# SCH_Base-robot_2026-06-25.net
KiCad netlist of a schematic drawn in EasyEDA
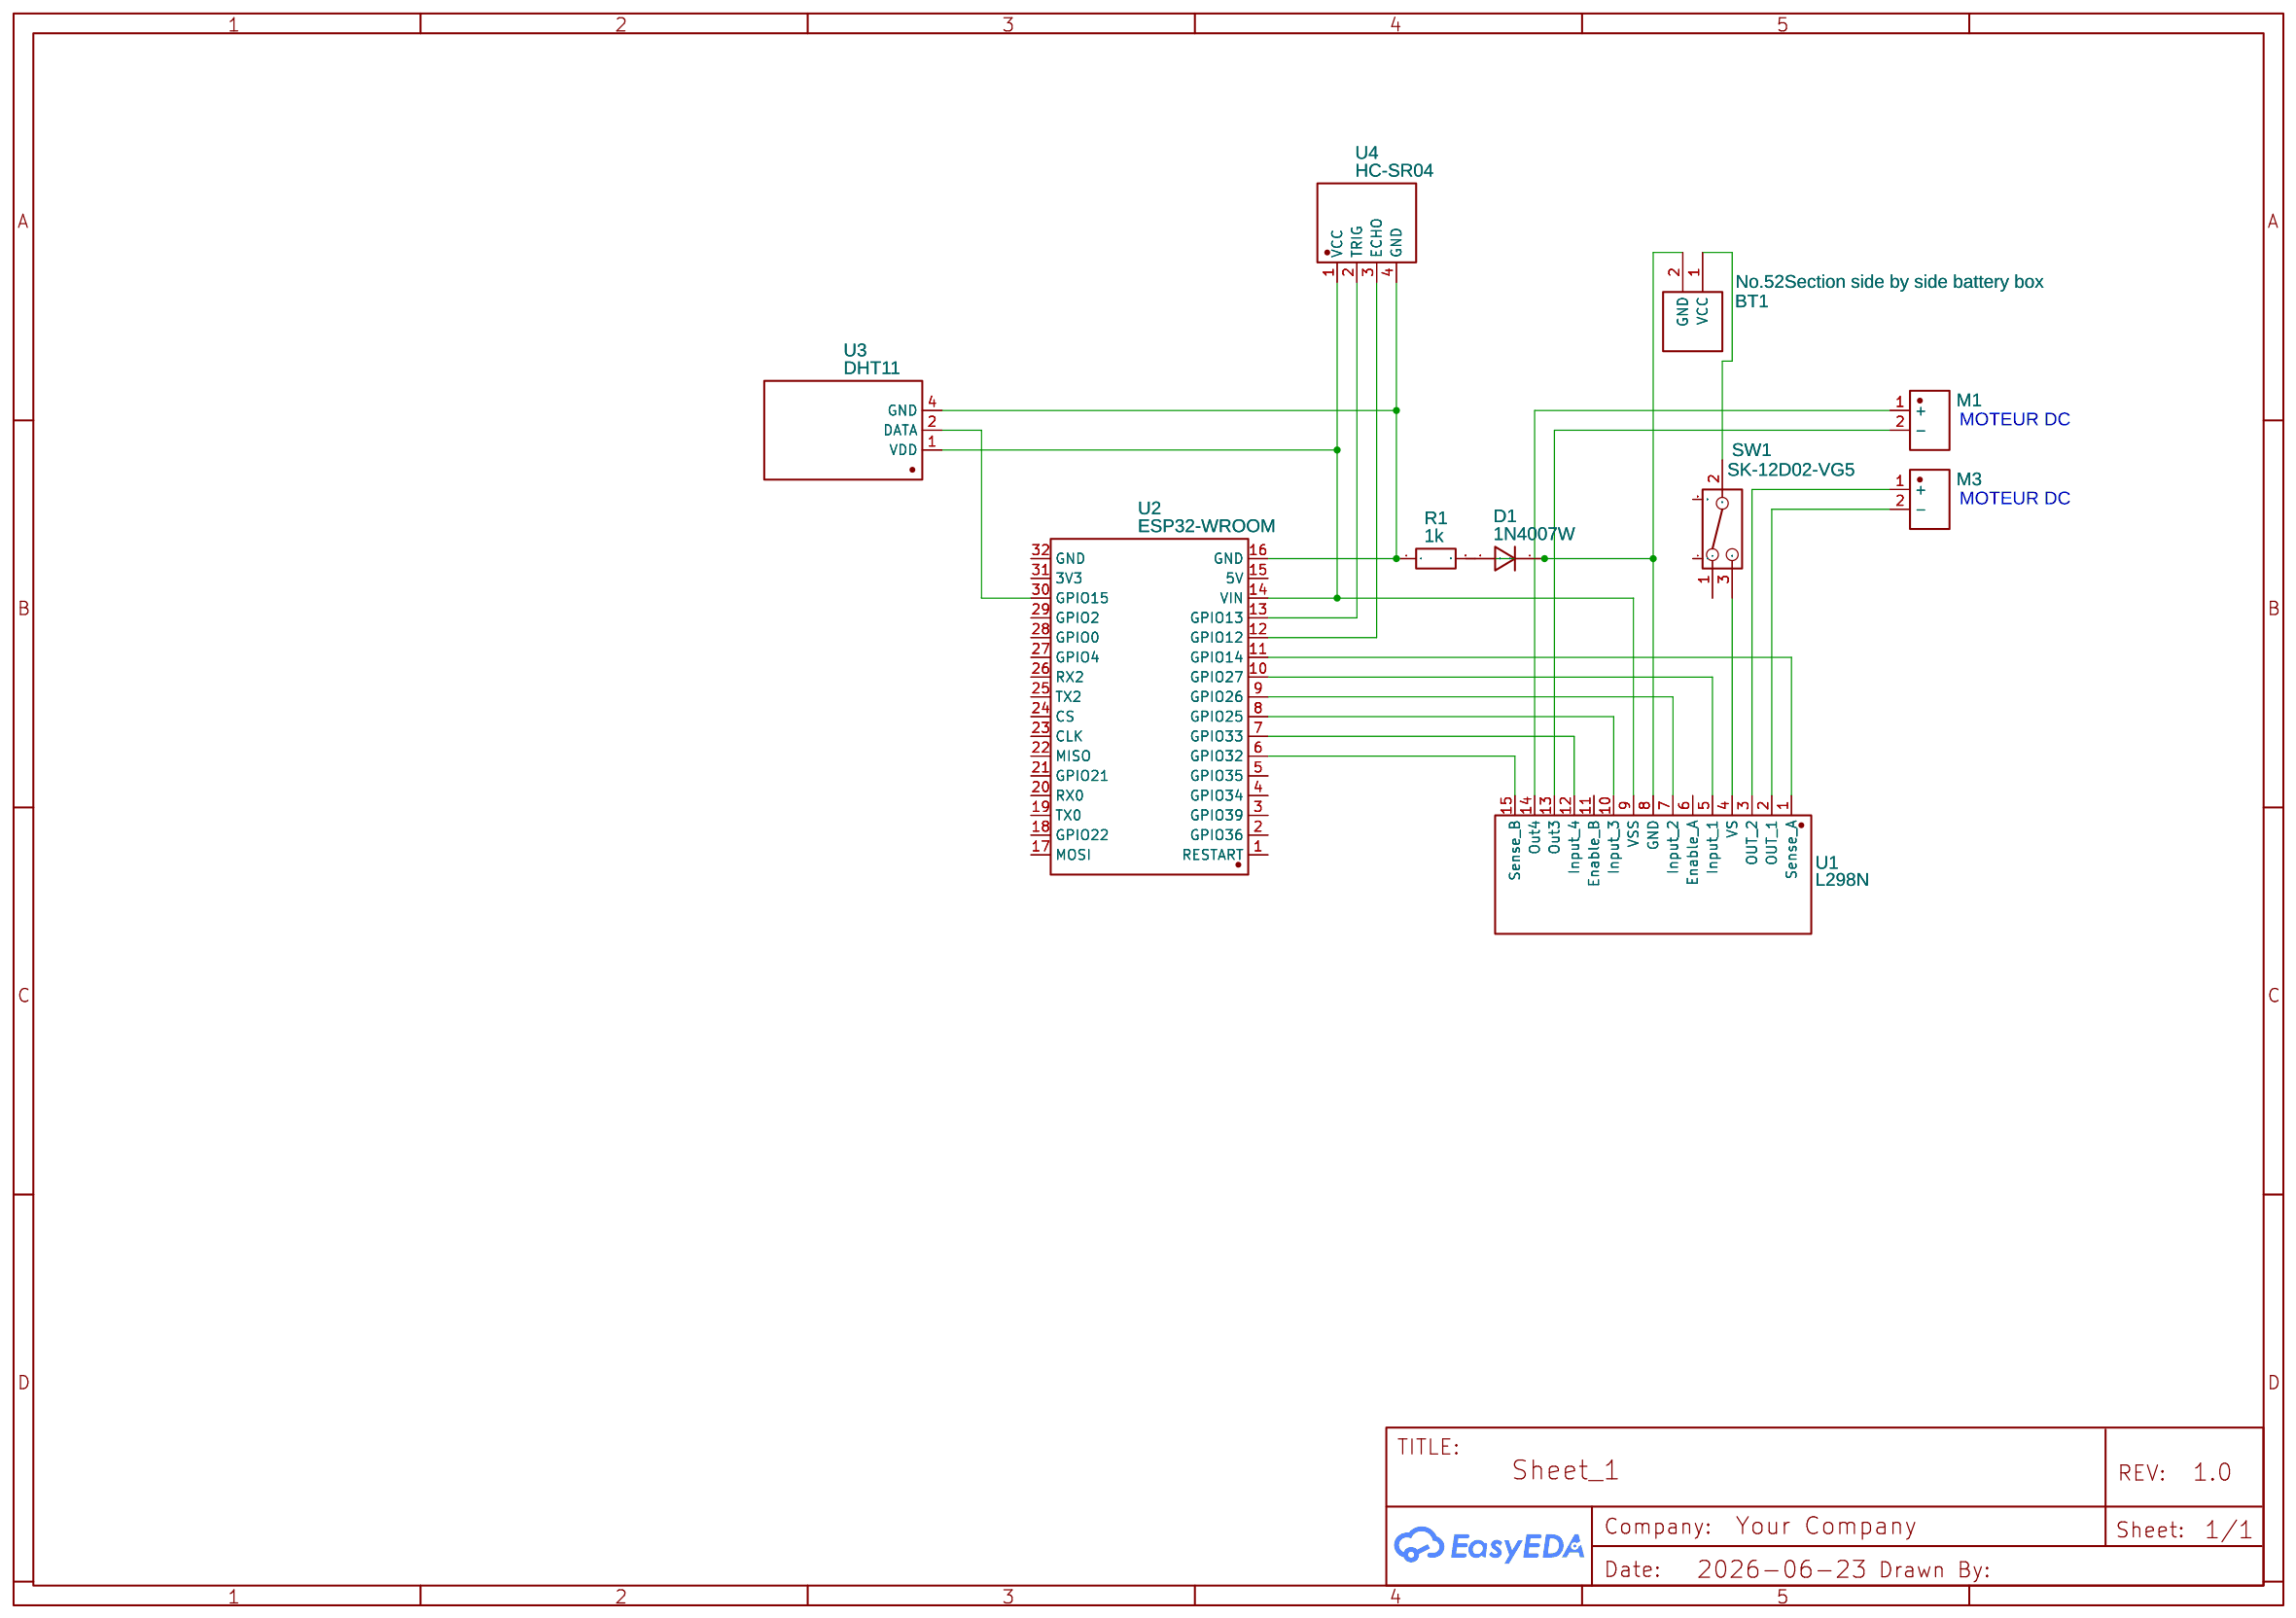
[diagram p0: Base Roulante]
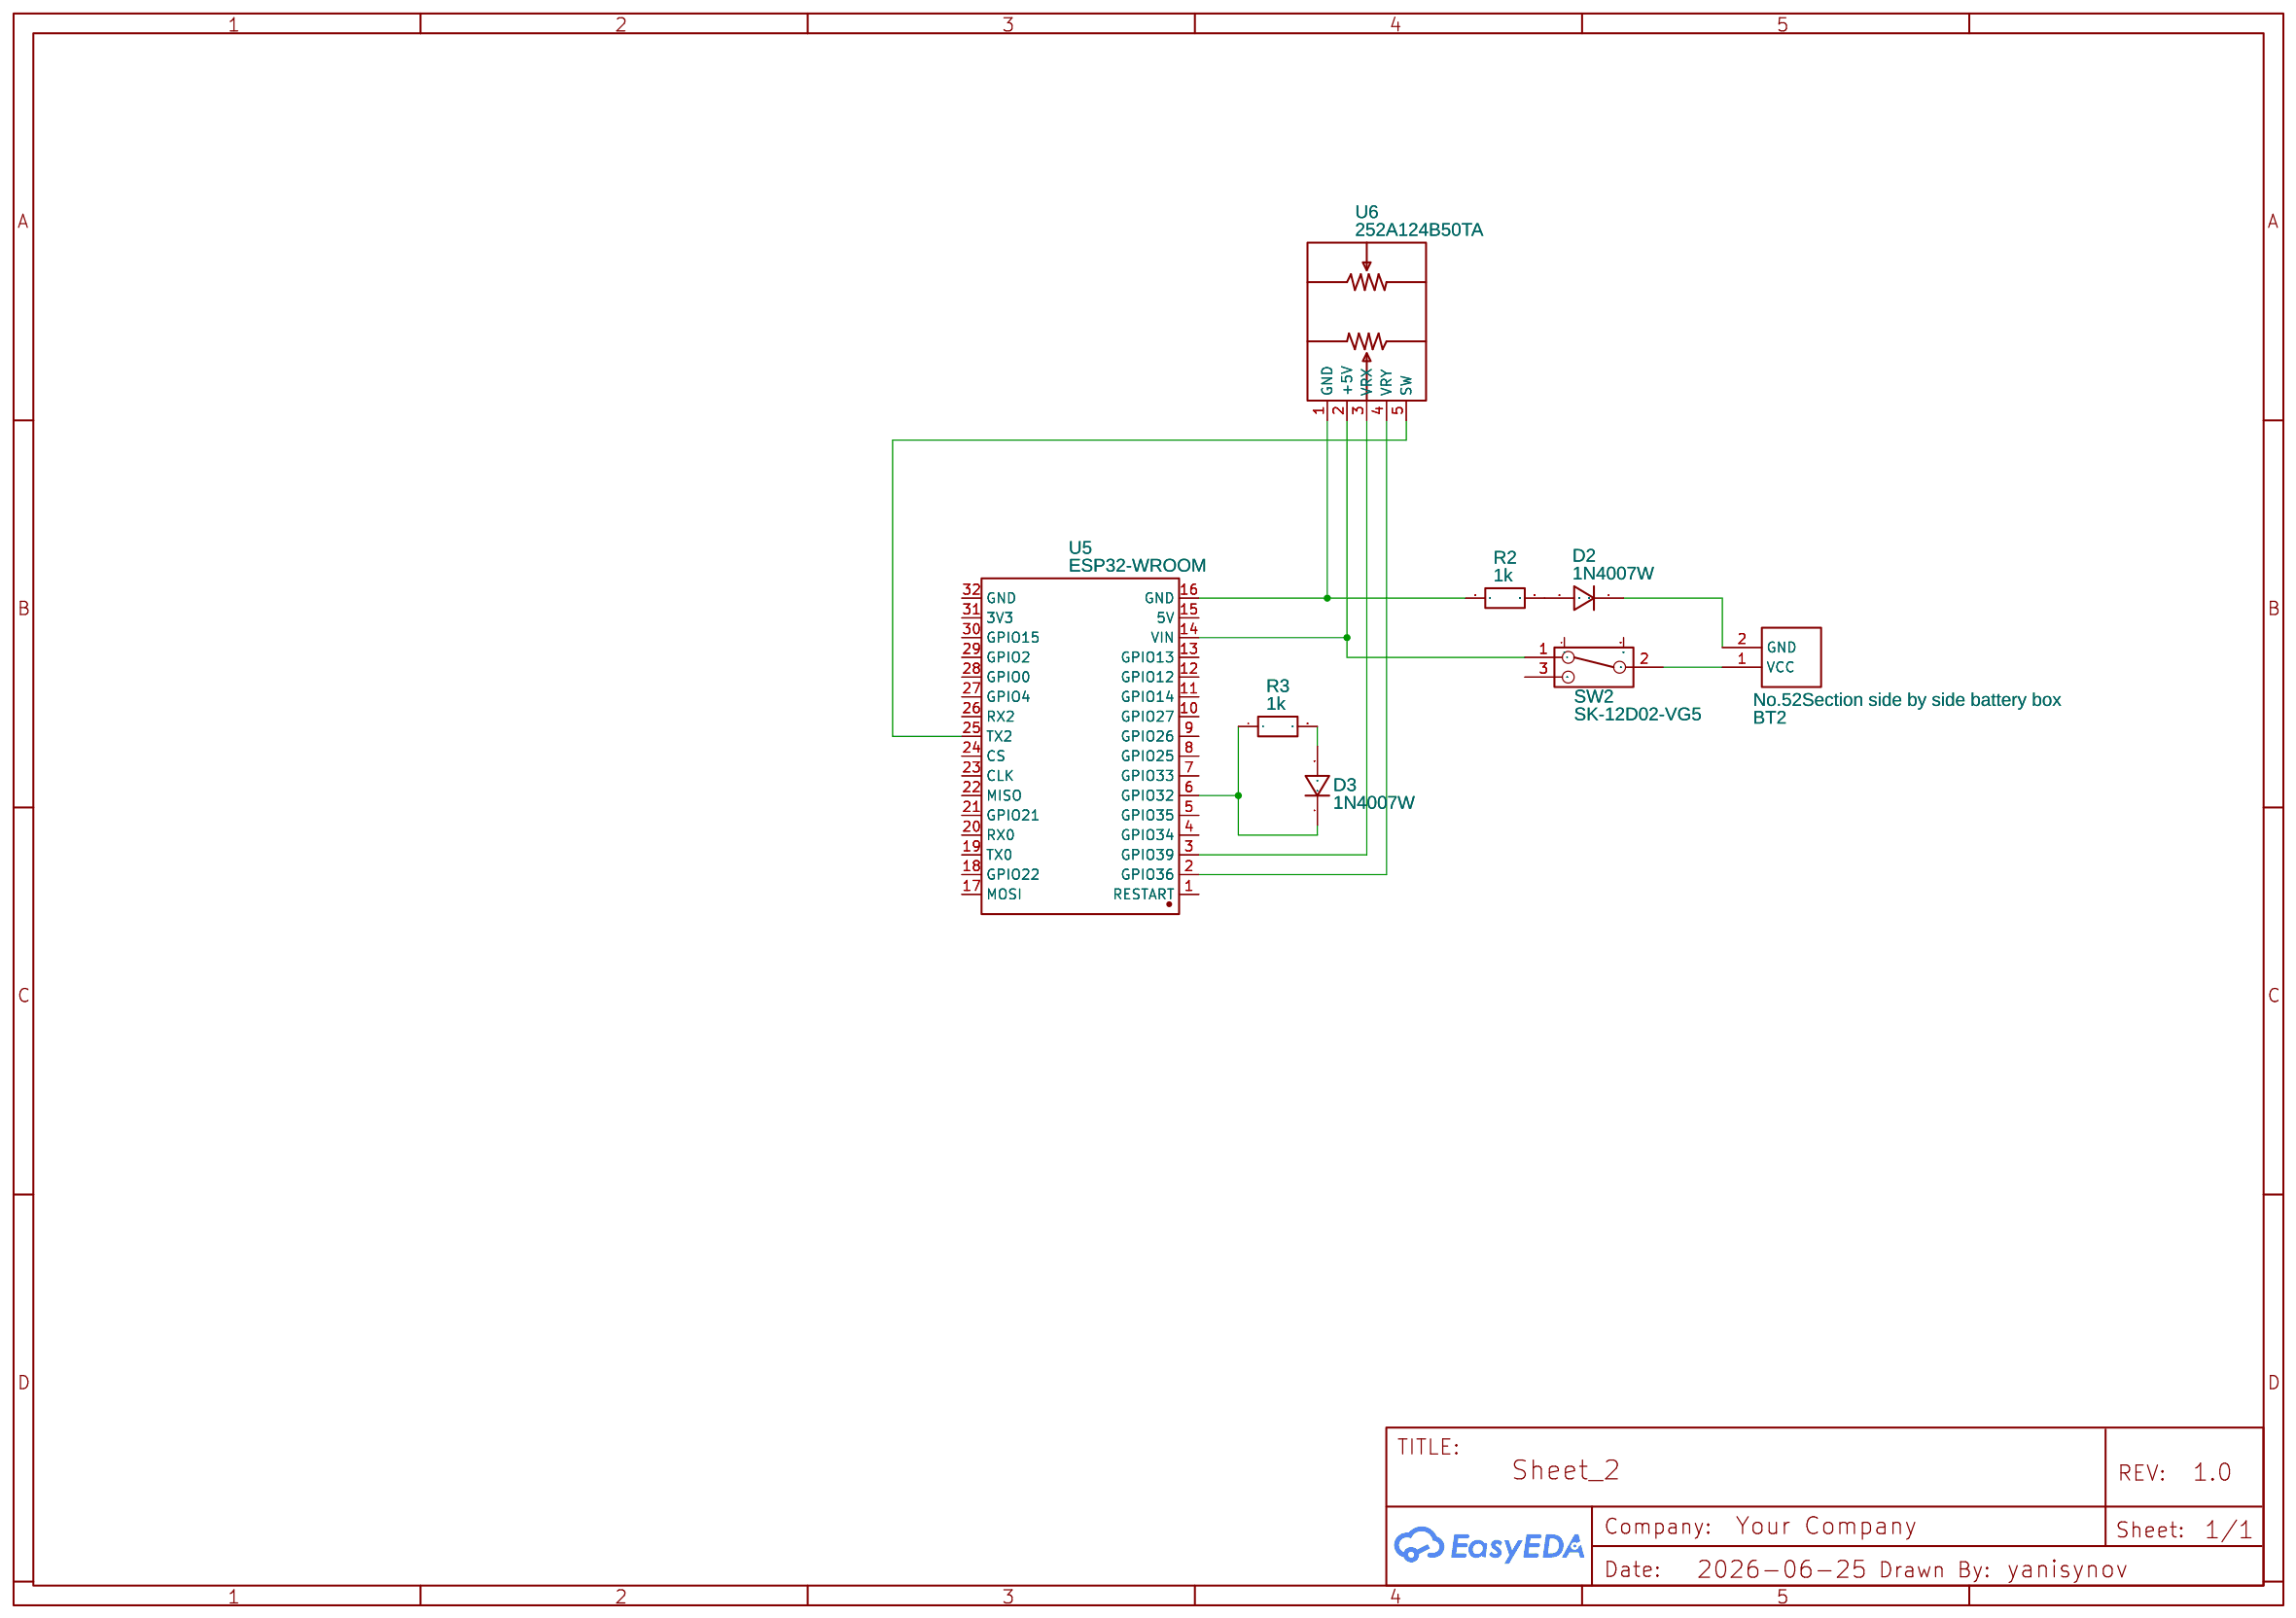
[diagram p1: Manette]

(export (version "E")
  (design (tool "Eeschema 10.0.6"))
  (components
    (comp (ref "BT1")
      (value "No.52Section side by side battery box")
      (fields (field (name "Manufacturer Part") "五号2节并列电池盒") (field (name "Manufacturer") "国产"))
      (libsource (lib "") (part "No.52Section side by side battery box"))
    )
    (comp (ref "D1")
      (value "1N4007W")
      (fields (field (name "Manufacturer") "BLUE ROCKET"))
      (libsource (lib "") (part "1N4007W"))
    )
    (comp (ref "M1")
      (value "MOTEUR DC")
      (fields (field (name "Manufacturer Part") "Z4TH3B0791626") (field (name "Manufacturer") "KOTL(金龙机电)"))
      (libsource (lib "") (part "Z4TH3B0791626"))
    )
    (comp (ref "M3")
      (value "MOTEUR DC")
      (fields (field (name "Manufacturer Part") "Z4TH3B0791626") (field (name "Manufacturer") "KOTL(金龙机电)"))
      (libsource (lib "") (part "Z4TH3B0791626"))
    )
    (comp (ref "R1") (value "1k") (libsource (lib "") (part "R_0603_EU")))
    (comp (ref "SW1")
      (value "SK-12D02-VG5")
      (fields (field (name "Manufacturer") "Rectangular Connectors - Contacts"))
      (libsource (lib "") (part "SK-12D02-VG5"))
    )
    (comp (ref "U1")
      (value "L298N")
      (fields (field (name "Manufacturer") "HGSEMI(华冠)"))
      (libsource (lib "") (part "L298N"))
    )
    (comp (ref "U2")
      (value "ESP32-WROOM")
      (fields (field (name "Manufacturer Part") "ESP32-WROOM-32U(16MB)"))
      (libsource (lib "") (part "ESP32-WROOM"))
    )
    (comp (ref "U3")
      (value "DHT11")
      (fields (field (name "Manufacturer") "广州奥松"))
      (libsource (lib "") (part "DHT11"))
    )
    (comp (ref "U4")
      (value "HC-SR04")
      (fields (field (name "Manufacturer") "Universal Microelectronics"))
      (libsource (lib "") (part "HC-SR04"))
    )
    (comp (ref "BT2")
      (value "No.52Section side by side battery box")
      (fields (field (name "Manufacturer Part") "五号2节并列电池盒") (field (name "Manufacturer") "国产"))
      (libsource (lib "") (part "No.52Section side by side battery box"))
    )
    (comp (ref "D2")
      (value "1N4007W")
      (fields (field (name "Manufacturer") "BLUE ROCKET"))
      (libsource (lib "") (part "1N4007W"))
    )
    (comp (ref "D3")
      (value "1N4007W")
      (fields (field (name "Manufacturer") "BLUE ROCKET"))
      (libsource (lib "") (part "1N4007W_1"))
    )
    (comp (ref "R2") (value "1k") (libsource (lib "") (part "R_0603_EU")))
    (comp (ref "R3") (value "1k") (libsource (lib "") (part "R_0603_EU")))
    (comp (ref "SW2")
      (value "SK-12D02-VG5")
      (fields (field (name "Manufacturer") "Rectangular Connectors - Contacts"))
      (libsource (lib "") (part "SK-12D02-VG5"))
    )
    (comp (ref "U5")
      (value "ESP32-WROOM")
      (fields (field (name "Manufacturer Part") "ESP32-WROOM-32U(16MB)"))
      (libsource (lib "") (part "ESP32-WROOM"))
    )
    (comp (ref "U6")
      (value "252A124B50TA")
      (fields (field (name "Manufacturer") "CTS(西迪斯)"))
      (libsource (lib "") (part "252A124B50TA"))
    )
  )
  (nets
    (net (code "1") (name "Net-(BT1-GND)") (class "Default")
      (node (ref "BT1") (pin "2") (pinfunction "GND_2") (pintype "unspecified"))
      (node (ref "D1") (pin "1") (pinfunction "1_1") (pintype "unspecified"))
      (node (ref "R1") (pin "2") (pinfunction "2_2") (pintype "unspecified"))
      (node (ref "U1") (pin "8") (pinfunction "GND_8") (pintype "unspecified"))
    )
    (net (code "2") (name "Net-(BT1-VCC)") (class "Default")
      (node (ref "BT1") (pin "1") (pinfunction "VCC_1") (pintype "unspecified"))
      (node (ref "SW1") (pin "2") (pinfunction "2_2") (pintype "unspecified"))
    )
    (net (code "3") (name "Net-(BT2-GND)") (class "Default")
      (node (ref "BT2") (pin "2") (pinfunction "GND_2") (pintype "unspecified"))
      (node (ref "D2") (pin "1") (pinfunction "1_1") (pintype "unspecified"))
    )
    (net (code "4") (name "Net-(BT2-VCC)") (class "Default")
      (node (ref "BT2") (pin "1") (pinfunction "VCC_1") (pintype "unspecified"))
      (node (ref "SW2") (pin "2") (pinfunction "2_2") (pintype "unspecified"))
    )
    (net (code "5") (name "Net-(D2-Pad2)") (class "Default")
      (node (ref "D2") (pin "2") (pinfunction "2_2") (pintype "unspecified"))
      (node (ref "R2") (pin "2") (pinfunction "2_2") (pintype "unspecified"))
    )
    (net (code "6") (name "Net-(D3-Pad2)") (class "Default")
      (node (ref "D3") (pin "2") (pinfunction "2_2") (pintype "unspecified"))
      (node (ref "R3") (pin "2") (pinfunction "2_2") (pintype "unspecified"))
    )
    (net (code "7") (name "Net-(M1-+)") (class "Default")
      (node (ref "M1") (pin "1") (pinfunction "+_1") (pintype "unspecified"))
      (node (ref "U1") (pin "14") (pinfunction "Out4_14") (pintype "unspecified"))
    )
    (net (code "8") (name "Net-(M1--)") (class "Default")
      (node (ref "M1") (pin "2") (pinfunction "-_2") (pintype "unspecified"))
      (node (ref "U1") (pin "13") (pinfunction "Out3_13") (pintype "unspecified"))
    )
    (net (code "9") (name "Net-(M3-+)") (class "Default")
      (node (ref "M3") (pin "1") (pinfunction "+_1") (pintype "unspecified"))
      (node (ref "U1") (pin "3") (pinfunction "OUT_2_3") (pintype "unspecified"))
    )
    (net (code "10") (name "Net-(M3--)") (class "Default")
      (node (ref "M3") (pin "2") (pinfunction "-_2") (pintype "unspecified"))
      (node (ref "U1") (pin "2") (pinfunction "OUT_1_2") (pintype "unspecified"))
    )
    (net (code "11") (name "Net-(U1-Input_1)") (class "Default")
      (node (ref "U1") (pin "5") (pinfunction "Input_1_5") (pintype "unspecified"))
      (node (ref "U2") (pin "10") (pinfunction "GPIO27_10") (pintype "unspecified"))
    )
    (net (code "12") (name "Net-(U1-Input_2)") (class "Default")
      (node (ref "U1") (pin "7") (pinfunction "Input_2_7") (pintype "unspecified"))
      (node (ref "U2") (pin "9") (pinfunction "GPIO26_9") (pintype "unspecified"))
    )
    (net (code "13") (name "Net-(U1-Input_3)") (class "Default")
      (node (ref "U1") (pin "10") (pinfunction "Input_3_10") (pintype "unspecified"))
      (node (ref "U2") (pin "8") (pinfunction "GPIO25_8") (pintype "unspecified"))
    )
    (net (code "14") (name "Net-(U1-Input_4)") (class "Default")
      (node (ref "U1") (pin "12") (pinfunction "Input_4_12") (pintype "unspecified"))
      (node (ref "U2") (pin "7") (pinfunction "GPIO33_7") (pintype "unspecified"))
    )
    (net (code "15") (name "Net-(U1-Sense_A)") (class "Default")
      (node (ref "U1") (pin "1") (pinfunction "Sense_A_1") (pintype "unspecified"))
      (node (ref "U2") (pin "11") (pinfunction "GPIO14_11") (pintype "unspecified"))
    )
    (net (code "16") (name "Net-(U1-Sense_B)") (class "Default")
      (node (ref "U1") (pin "15") (pinfunction "Sense_B_15") (pintype "unspecified"))
      (node (ref "U2") (pin "6") (pinfunction "GPIO32_6") (pintype "unspecified"))
    )
    (net (code "17") (name "Net-(U1-VS)") (class "Default")
      (node (ref "SW1") (pin "3") (pinfunction "3_3") (pintype "unspecified"))
      (node (ref "U1") (pin "4") (pinfunction "VS_4") (pintype "unspecified"))
    )
    (net (code "18") (name "Net-(U1-VSS)") (class "Default")
      (node (ref "U1") (pin "9") (pinfunction "VSS_9") (pintype "unspecified"))
      (node (ref "U2") (pin "14") (pinfunction "VIN_14") (pintype "unspecified"))
      (node (ref "U3") (pin "1") (pinfunction "VDD_1") (pintype "unspecified"))
      (node (ref "U4") (pin "1") (pinfunction "VCC_1") (pintype "unspecified"))
    )
    (net (code "19") (name "Net-(U2-GPIO12)") (class "Default")
      (node (ref "U2") (pin "12") (pinfunction "GPIO12_12") (pintype "unspecified"))
      (node (ref "U4") (pin "3") (pinfunction "ECHO_3") (pintype "unspecified"))
    )
    (net (code "20") (name "Net-(U2-GPIO13)") (class "Default")
      (node (ref "U2") (pin "13") (pinfunction "GPIO13_13") (pintype "unspecified"))
      (node (ref "U4") (pin "2") (pinfunction "TRIG_2") (pintype "unspecified"))
    )
    (net (code "21") (name "Net-(U2-GPIO15)") (class "Default")
      (node (ref "U2") (pin "30") (pinfunction "GPIO15_30") (pintype "unspecified"))
      (node (ref "U3") (pin "2") (pinfunction "DATA_2") (pintype "unspecified"))
    )
    (net (code "22") (name "Net-(U3-GND)") (class "Default")
      (node (ref "R1") (pin "1") (pinfunction "1_1") (pintype "unspecified"))
      (node (ref "U2") (pin "16") (pinfunction "GND_16") (pintype "unspecified"))
      (node (ref "U3") (pin "4") (pinfunction "GND_4") (pintype "unspecified"))
      (node (ref "U4") (pin "4") (pinfunction "GND_4") (pintype "unspecified"))
    )
    (net (code "23") (name "Net-(U5-GPIO32)") (class "Default")
      (node (ref "D3") (pin "1") (pinfunction "1_1") (pintype "unspecified"))
      (node (ref "R3") (pin "1") (pinfunction "1_1") (pintype "unspecified"))
      (node (ref "U5") (pin "6") (pinfunction "GPIO32_6") (pintype "unspecified"))
    )
    (net (code "24") (name "Net-(U5-GPIO36)") (class "Default")
      (node (ref "U5") (pin "2") (pinfunction "GPIO36_2") (pintype "unspecified"))
      (node (ref "U6") (pin "4") (pinfunction "VRY_4") (pintype "unspecified"))
    )
    (net (code "25") (name "Net-(U5-GPIO39)") (class "Default")
      (node (ref "U5") (pin "3") (pinfunction "GPIO39_3") (pintype "unspecified"))
      (node (ref "U6") (pin "3") (pinfunction "VRX_3") (pintype "unspecified"))
    )
    (net (code "26") (name "Net-(U5-TX2)") (class "Default")
      (node (ref "U5") (pin "25") (pinfunction "TX2_25") (pintype "unspecified"))
      (node (ref "U6") (pin "5") (pinfunction "SW_5") (pintype "unspecified"))
    )
    (net (code "27") (name "Net-(U5-VIN)") (class "Default")
      (node (ref "SW2") (pin "1") (pinfunction "1_1") (pintype "unspecified"))
      (node (ref "U5") (pin "14") (pinfunction "VIN_14") (pintype "unspecified"))
      (node (ref "U6") (pin "2") (pinfunction "+5V_2") (pintype "unspecified"))
    )
    (net (code "28") (name "Net-(U6-GND)") (class "Default")
      (node (ref "R2") (pin "1") (pinfunction "1_1") (pintype "unspecified"))
      (node (ref "U5") (pin "16") (pinfunction "GND_16") (pintype "unspecified"))
      (node (ref "U6") (pin "1") (pinfunction "GND_1") (pintype "unspecified"))
    )
    (net (code "29") (name "unconnected-(D1-Pad2)") (class "Default")
      (node (ref "D1") (pin "2") (pinfunction "2_2") (pintype "unspecified"))
    )
    (net (code "30") (name "unconnected-(SW1-Pad1)") (class "Default")
      (node (ref "SW1") (pin "1") (pinfunction "1_1") (pintype "unspecified"))
    )
    (net (code "31") (name "unconnected-(SW1-Pad4)") (class "Default")
      (node (ref "SW1") (pin "4") (pinfunction "4_4") (pintype "unspecified"))
    )
    (net (code "32") (name "unconnected-(SW1-Pad5)") (class "Default")
      (node (ref "SW1") (pin "5") (pinfunction "5_5") (pintype "unspecified"))
    )
    (net (code "33") (name "unconnected-(SW2-Pad3)") (class "Default")
      (node (ref "SW2") (pin "3") (pinfunction "3_3") (pintype "unspecified"))
    )
    (net (code "34") (name "unconnected-(SW2-Pad4)") (class "Default")
      (node (ref "SW2") (pin "4") (pinfunction "4_4") (pintype "unspecified"))
    )
    (net (code "35") (name "unconnected-(SW2-Pad5)") (class "Default")
      (node (ref "SW2") (pin "5") (pinfunction "5_5") (pintype "unspecified"))
    )
    (net (code "36") (name "unconnected-(U1-Enable_A-Pad6)") (class "Default")
      (node (ref "U1") (pin "6") (pinfunction "Enable_A_6") (pintype "unspecified"))
    )
    (net (code "37") (name "unconnected-(U1-Enable_B-Pad11)") (class "Default")
      (node (ref "U1") (pin "11") (pinfunction "Enable_B_11") (pintype "unspecified"))
    )
    (net (code "38") (name "unconnected-(U2-3V3-Pad31)") (class "Default")
      (node (ref "U2") (pin "31") (pinfunction "3V3_31") (pintype "unspecified"))
    )
    (net (code "39") (name "unconnected-(U2-5V-Pad15)") (class "Default")
      (node (ref "U2") (pin "15") (pinfunction "5V_15") (pintype "unspecified"))
    )
    (net (code "40") (name "unconnected-(U2-CLK-Pad23)") (class "Default")
      (node (ref "U2") (pin "23") (pinfunction "CLK_23") (pintype "unspecified"))
    )
    (net (code "41") (name "unconnected-(U2-CS-Pad24)") (class "Default")
      (node (ref "U2") (pin "24") (pinfunction "CS_24") (pintype "unspecified"))
    )
    (net (code "42") (name "unconnected-(U2-GND-Pad32)") (class "Default")
      (node (ref "U2") (pin "32") (pinfunction "GND_32") (pintype "unspecified"))
    )
    (net (code "43") (name "unconnected-(U2-GPIO0-Pad28)") (class "Default")
      (node (ref "U2") (pin "28") (pinfunction "GPIO0_28") (pintype "unspecified"))
    )
    (net (code "44") (name "unconnected-(U2-GPIO2-Pad29)") (class "Default")
      (node (ref "U2") (pin "29") (pinfunction "GPIO2_29") (pintype "unspecified"))
    )
    (net (code "45") (name "unconnected-(U2-GPIO4-Pad27)") (class "Default")
      (node (ref "U2") (pin "27") (pinfunction "GPIO4_27") (pintype "unspecified"))
    )
    (net (code "46") (name "unconnected-(U2-GPIO21-Pad21)") (class "Default")
      (node (ref "U2") (pin "21") (pinfunction "GPIO21_21") (pintype "unspecified"))
    )
    (net (code "47") (name "unconnected-(U2-GPIO22-Pad18)") (class "Default")
      (node (ref "U2") (pin "18") (pinfunction "GPIO22_18") (pintype "unspecified"))
    )
    (net (code "48") (name "unconnected-(U2-GPIO34-Pad4)") (class "Default")
      (node (ref "U2") (pin "4") (pinfunction "GPIO34_4") (pintype "unspecified"))
    )
    (net (code "49") (name "unconnected-(U2-GPIO35-Pad5)") (class "Default")
      (node (ref "U2") (pin "5") (pinfunction "GPIO35_5") (pintype "unspecified"))
    )
    (net (code "50") (name "unconnected-(U2-GPIO36-Pad2)") (class "Default")
      (node (ref "U2") (pin "2") (pinfunction "GPIO36_2") (pintype "unspecified"))
    )
    (net (code "51") (name "unconnected-(U2-GPIO39-Pad3)") (class "Default")
      (node (ref "U2") (pin "3") (pinfunction "GPIO39_3") (pintype "unspecified"))
    )
    (net (code "52") (name "unconnected-(U2-MISO-Pad22)") (class "Default")
      (node (ref "U2") (pin "22") (pinfunction "MISO_22") (pintype "unspecified"))
    )
    (net (code "53") (name "unconnected-(U2-MOSI-Pad17)") (class "Default")
      (node (ref "U2") (pin "17") (pinfunction "MOSI_17") (pintype "unspecified"))
    )
    (net (code "54") (name "unconnected-(U2-RESTART-Pad1)") (class "Default")
      (node (ref "U2") (pin "1") (pinfunction "RESTART_1") (pintype "unspecified"))
    )
    (net (code "55") (name "unconnected-(U2-RX0-Pad20)") (class "Default")
      (node (ref "U2") (pin "20") (pinfunction "RX0_20") (pintype "unspecified"))
    )
    (net (code "56") (name "unconnected-(U2-RX2-Pad26)") (class "Default")
      (node (ref "U2") (pin "26") (pinfunction "RX2_26") (pintype "unspecified"))
    )
    (net (code "57") (name "unconnected-(U2-TX0-Pad19)") (class "Default")
      (node (ref "U2") (pin "19") (pinfunction "TX0_19") (pintype "unspecified"))
    )
    (net (code "58") (name "unconnected-(U2-TX2-Pad25)") (class "Default")
      (node (ref "U2") (pin "25") (pinfunction "TX2_25") (pintype "unspecified"))
    )
    (net (code "59") (name "unconnected-(U5-3V3-Pad31)") (class "Default")
      (node (ref "U5") (pin "31") (pinfunction "3V3_31") (pintype "unspecified"))
    )
    (net (code "60") (name "unconnected-(U5-5V-Pad15)") (class "Default")
      (node (ref "U5") (pin "15") (pinfunction "5V_15") (pintype "unspecified"))
    )
    (net (code "61") (name "unconnected-(U5-CLK-Pad23)") (class "Default")
      (node (ref "U5") (pin "23") (pinfunction "CLK_23") (pintype "unspecified"))
    )
    (net (code "62") (name "unconnected-(U5-CS-Pad24)") (class "Default")
      (node (ref "U5") (pin "24") (pinfunction "CS_24") (pintype "unspecified"))
    )
    (net (code "63") (name "unconnected-(U5-GND-Pad32)") (class "Default")
      (node (ref "U5") (pin "32") (pinfunction "GND_32") (pintype "unspecified"))
    )
    (net (code "64") (name "unconnected-(U5-GPIO0-Pad28)") (class "Default")
      (node (ref "U5") (pin "28") (pinfunction "GPIO0_28") (pintype "unspecified"))
    )
    (net (code "65") (name "unconnected-(U5-GPIO2-Pad29)") (class "Default")
      (node (ref "U5") (pin "29") (pinfunction "GPIO2_29") (pintype "unspecified"))
    )
    (net (code "66") (name "unconnected-(U5-GPIO4-Pad27)") (class "Default")
      (node (ref "U5") (pin "27") (pinfunction "GPIO4_27") (pintype "unspecified"))
    )
    (net (code "67") (name "unconnected-(U5-GPIO12-Pad12)") (class "Default")
      (node (ref "U5") (pin "12") (pinfunction "GPIO12_12") (pintype "unspecified"))
    )
    (net (code "68") (name "unconnected-(U5-GPIO13-Pad13)") (class "Default")
      (node (ref "U5") (pin "13") (pinfunction "GPIO13_13") (pintype "unspecified"))
    )
    (net (code "69") (name "unconnected-(U5-GPIO14-Pad11)") (class "Default")
      (node (ref "U5") (pin "11") (pinfunction "GPIO14_11") (pintype "unspecified"))
    )
    (net (code "70") (name "unconnected-(U5-GPIO15-Pad30)") (class "Default")
      (node (ref "U5") (pin "30") (pinfunction "GPIO15_30") (pintype "unspecified"))
    )
    (net (code "71") (name "unconnected-(U5-GPIO21-Pad21)") (class "Default")
      (node (ref "U5") (pin "21") (pinfunction "GPIO21_21") (pintype "unspecified"))
    )
    (net (code "72") (name "unconnected-(U5-GPIO22-Pad18)") (class "Default")
      (node (ref "U5") (pin "18") (pinfunction "GPIO22_18") (pintype "unspecified"))
    )
    (net (code "73") (name "unconnected-(U5-GPIO25-Pad8)") (class "Default")
      (node (ref "U5") (pin "8") (pinfunction "GPIO25_8") (pintype "unspecified"))
    )
    (net (code "74") (name "unconnected-(U5-GPIO26-Pad9)") (class "Default")
      (node (ref "U5") (pin "9") (pinfunction "GPIO26_9") (pintype "unspecified"))
    )
    (net (code "75") (name "unconnected-(U5-GPIO27-Pad10)") (class "Default")
      (node (ref "U5") (pin "10") (pinfunction "GPIO27_10") (pintype "unspecified"))
    )
    (net (code "76") (name "unconnected-(U5-GPIO33-Pad7)") (class "Default")
      (node (ref "U5") (pin "7") (pinfunction "GPIO33_7") (pintype "unspecified"))
    )
    (net (code "77") (name "unconnected-(U5-GPIO34-Pad4)") (class "Default")
      (node (ref "U5") (pin "4") (pinfunction "GPIO34_4") (pintype "unspecified"))
    )
    (net (code "78") (name "unconnected-(U5-GPIO35-Pad5)") (class "Default")
      (node (ref "U5") (pin "5") (pinfunction "GPIO35_5") (pintype "unspecified"))
    )
    (net (code "79") (name "unconnected-(U5-MISO-Pad22)") (class "Default")
      (node (ref "U5") (pin "22") (pinfunction "MISO_22") (pintype "unspecified"))
    )
    (net (code "80") (name "unconnected-(U5-MOSI-Pad17)") (class "Default")
      (node (ref "U5") (pin "17") (pinfunction "MOSI_17") (pintype "unspecified"))
    )
    (net (code "81") (name "unconnected-(U5-RESTART-Pad1)") (class "Default")
      (node (ref "U5") (pin "1") (pinfunction "RESTART_1") (pintype "unspecified"))
    )
    (net (code "82") (name "unconnected-(U5-RX0-Pad20)") (class "Default")
      (node (ref "U5") (pin "20") (pinfunction "RX0_20") (pintype "unspecified"))
    )
    (net (code "83") (name "unconnected-(U5-RX2-Pad26)") (class "Default")
      (node (ref "U5") (pin "26") (pinfunction "RX2_26") (pintype "unspecified"))
    )
    (net (code "84") (name "unconnected-(U5-TX0-Pad19)") (class "Default")
      (node (ref "U5") (pin "19") (pinfunction "TX0_19") (pintype "unspecified"))
    )
  )
)
